# Netzteil_5V.net
KiCad netlist of a schematic drawn in EAGLE
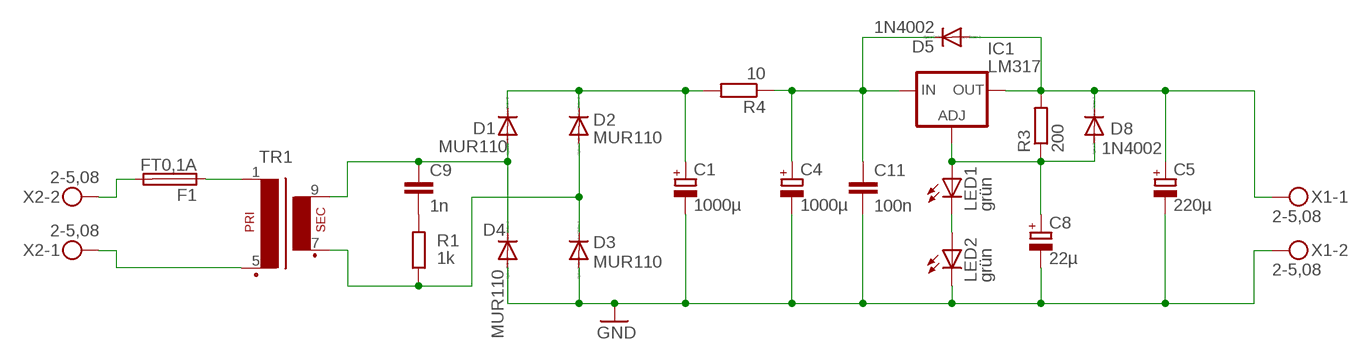
[diagram p0: schematic, sheet 1]

(export (version "E")
  (design (tool "Eeschema 10.0.6"))
  (components
    (comp (ref "C1")
      (value "1000µ")
      (footprint "eagle-import:E5-13")
      (libsource (lib "eagle-import") (part "CPOL-EUE5-13"))
    )
    (comp (ref "C4")
      (value "1000µ")
      (footprint "eagle-import:E5-13")
      (libsource (lib "eagle-import") (part "CPOL-EUE5-13"))
    )
    (comp (ref "C5")
      (value "220µ")
      (footprint "eagle-import:E3,5-8")
      (libsource (lib "eagle-import") (part "CPOL-EUE3.5-8"))
    )
    (comp (ref "C8")
      (value "22µ")
      (footprint "eagle-import:E2-5")
      (libsource (lib "eagle-import") (part "CPOL-EUE2-5"))
    )
    (comp (ref "C9")
      (value "1n")
      (footprint "eagle-import:C050-045X075")
      (libsource (lib "eagle-import") (part "C-EU050-045X075"))
    )
    (comp (ref "C11")
      (value "100n")
      (footprint "eagle-import:C050-025X075")
      (libsource (lib "eagle-import") (part "C-EU050-025X075"))
    )
    (comp (ref "D1")
      (value "MUR110")
      (footprint "eagle-import:DO41-10")
      (libsource (lib "eagle-import") (part "MUR150RL"))
    )
    (comp (ref "D2")
      (value "MUR110")
      (footprint "eagle-import:DO41-10")
      (libsource (lib "eagle-import") (part "MUR150RL"))
    )
    (comp (ref "D3")
      (value "MUR110")
      (footprint "eagle-import:DO41-10")
      (libsource (lib "eagle-import") (part "MUR150RL"))
    )
    (comp (ref "D4")
      (value "MUR110")
      (footprint "eagle-import:DO41-10")
      (libsource (lib "eagle-import") (part "MUR150RL"))
    )
    (comp (ref "D5")
      (value "1N4002")
      (footprint "eagle-import:DO41-10")
      (libsource (lib "eagle-import") (part "MUR150RL"))
    )
    (comp (ref "D8")
      (value "1N4002")
      (footprint "eagle-import:DO41-10")
      (libsource (lib "eagle-import") (part "MUR150RL"))
    )
    (comp (ref "F1")
      (value "FT0,1A")
      (footprint "eagle-import:19560")
      (fields (field (name "MPN") "56000001009"))
      (libsource (lib "eagle-import") (part "FUSE19560"))
    )
    (comp (ref "IC1")
      (value "LM317")
      (footprint "eagle-import:317TS")
      (libsource (lib "eagle-import") (part "LM317TS"))
    )
    (comp (ref "LED1")
      (value "grün")
      (footprint "eagle-import:LED3MM")
      (libsource (lib "eagle-import") (part "LED3MM"))
    )
    (comp (ref "LED2")
      (value "grün")
      (footprint "eagle-import:LED3MM")
      (libsource (lib "eagle-import") (part "LED3MM"))
    )
    (comp (ref "R1")
      (value "1k")
      (footprint "eagle-import:0207_10")
      (libsource (lib "eagle-import") (part "R-EU_0207/10"))
    )
    (comp (ref "R3")
      (value "200")
      (footprint "eagle-import:0207_10")
      (libsource (lib "eagle-import") (part "R-EU_0207/10"))
    )
    (comp (ref "R4")
      (value "10")
      (footprint "eagle-import:0617V")
      (libsource (lib "eagle-import") (part "R-EU_0617/5V"))
    )
    (comp (ref "TR1")
      (value "EI38-1")
      (footprint "eagle-import:EI38-1")
      (libsource (lib "eagle-import") (part "EI38-1"))
    )
    (comp (ref "X1")
      (value "2-5,08")
      (footprint "eagle-import:MKDSN1,5_2-5,08")
      (libsource (lib "eagle-import") (part "MKDSN1,5/2-5,08"))
    )
    (comp (ref "X2")
      (value "2-5,08")
      (footprint "eagle-import:MKDSN1,5_2-5,08")
      (libsource (lib "eagle-import") (part "MKDSN1,5/2-5,08"))
    )
  )
  (nets
    (net (code "1") (name "GND") (class "Default")
      (node (ref "C1") (pin "-") (pinfunction "-_-") (pintype "passive"))
      (node (ref "C11") (pin "2") (pinfunction "2_2") (pintype "passive"))
      (node (ref "C4") (pin "-") (pinfunction "-_-") (pintype "passive"))
      (node (ref "C5") (pin "-") (pinfunction "-_-") (pintype "passive"))
      (node (ref "C8") (pin "-") (pinfunction "-_-") (pintype "passive"))
      (node (ref "D3") (pin "A") (pinfunction "A_A") (pintype "passive"))
      (node (ref "D4") (pin "A") (pinfunction "A_A") (pintype "passive"))
      (node (ref "LED2") (pin "K") (pinfunction "C_K") (pintype "passive"))
      (node (ref "X1") (pin "2") (pinfunction "KL_2") (pintype "passive"))
    )
    (net (code "2") (name "Net-(C1-Pad+)") (class "Default")
      (node (ref "C1") (pin "+") (pinfunction "+_+") (pintype "passive"))
      (node (ref "D1") (pin "C") (pinfunction "C_C") (pintype "passive"))
      (node (ref "D2") (pin "C") (pinfunction "C_C") (pintype "passive"))
      (node (ref "R4") (pin "2") (pinfunction "2_2") (pintype "passive"))
    )
    (net (code "3") (name "Net-(C9-Pad2)") (class "Default")
      (node (ref "C9") (pin "2") (pinfunction "2_2") (pintype "passive"))
      (node (ref "R1") (pin "2") (pinfunction "2_2") (pintype "passive"))
    )
    (net (code "4") (name "Net-(IC1-ADJ)") (class "Default")
      (node (ref "C8") (pin "+") (pinfunction "+_+") (pintype "passive"))
      (node (ref "D8") (pin "A") (pinfunction "A_A") (pintype "passive"))
      (node (ref "IC1") (pin "1") (pinfunction "ADJ_1") (pintype "input"))
      (node (ref "LED1") (pin "A") (pinfunction "A_A") (pintype "passive"))
      (node (ref "R3") (pin "1") (pinfunction "1_1") (pintype "passive"))
    )
    (net (code "5") (name "Net-(IC1-IN)") (class "Default")
      (node (ref "C11") (pin "1") (pinfunction "1_1") (pintype "passive"))
      (node (ref "C4") (pin "+") (pinfunction "+_+") (pintype "passive"))
      (node (ref "D5") (pin "C") (pinfunction "C_C") (pintype "passive"))
      (node (ref "IC1") (pin "3") (pinfunction "IN_3") (pintype "input"))
      (node (ref "R4") (pin "1") (pinfunction "1_1") (pintype "passive"))
    )
    (net (code "6") (name "Net-(IC1-OUT)") (class "Default")
      (node (ref "C5") (pin "+") (pinfunction "+_+") (pintype "passive"))
      (node (ref "D5") (pin "A") (pinfunction "A_A") (pintype "passive"))
      (node (ref "D8") (pin "C") (pinfunction "C_C") (pintype "passive"))
      (node (ref "IC1") (pin "2") (pinfunction "OUT_2") (pintype "passive"))
      (node (ref "R3") (pin "2") (pinfunction "2_2") (pintype "passive"))
      (node (ref "X1") (pin "1") (pinfunction "KL_1") (pintype "passive"))
    )
    (net (code "7") (name "Net-(LED1-C)") (class "Default")
      (node (ref "LED1") (pin "K") (pinfunction "C_K") (pintype "passive"))
      (node (ref "LED2") (pin "A") (pinfunction "A_A") (pintype "passive"))
    )
    (net (code "8") (name "Net-(TR1-P1)") (class "Default")
      (node (ref "F1") (pin "1") (pinfunction "1_1") (pintype "passive"))
      (node (ref "TR1") (pin "1") (pinfunction "P1_1") (pintype "passive"))
    )
    (net (code "9") (name "Net-(TR1-P2)") (class "Default")
      (node (ref "TR1") (pin "5") (pinfunction "P2_5") (pintype "passive"))
      (node (ref "X2") (pin "1") (pinfunction "KL_1") (pintype "passive"))
    )
    (net (code "10") (name "Net-(TR1-S3)") (class "Default")
      (node (ref "D2") (pin "A") (pinfunction "A_A") (pintype "passive"))
      (node (ref "D3") (pin "C") (pinfunction "C_C") (pintype "passive"))
      (node (ref "R1") (pin "1") (pinfunction "1_1") (pintype "passive"))
      (node (ref "TR1") (pin "7") (pinfunction "S3_7") (pintype "passive"))
    )
    (net (code "11") (name "Net-(TR1-S4)") (class "Default")
      (node (ref "C9") (pin "1") (pinfunction "1_1") (pintype "passive"))
      (node (ref "D1") (pin "A") (pinfunction "A_A") (pintype "passive"))
      (node (ref "D4") (pin "C") (pinfunction "C_C") (pintype "passive"))
      (node (ref "TR1") (pin "9") (pinfunction "S4_9") (pintype "passive"))
    )
    (net (code "12") (name "Net-(X2B-KL)") (class "Default")
      (node (ref "F1") (pin "2") (pinfunction "2_2") (pintype "passive"))
      (node (ref "X2") (pin "2") (pinfunction "KL_2") (pintype "passive"))
    )
  )
)
